# wemos_gpio_7x.net
KiCad netlist of a schematic drawn in EAGLE
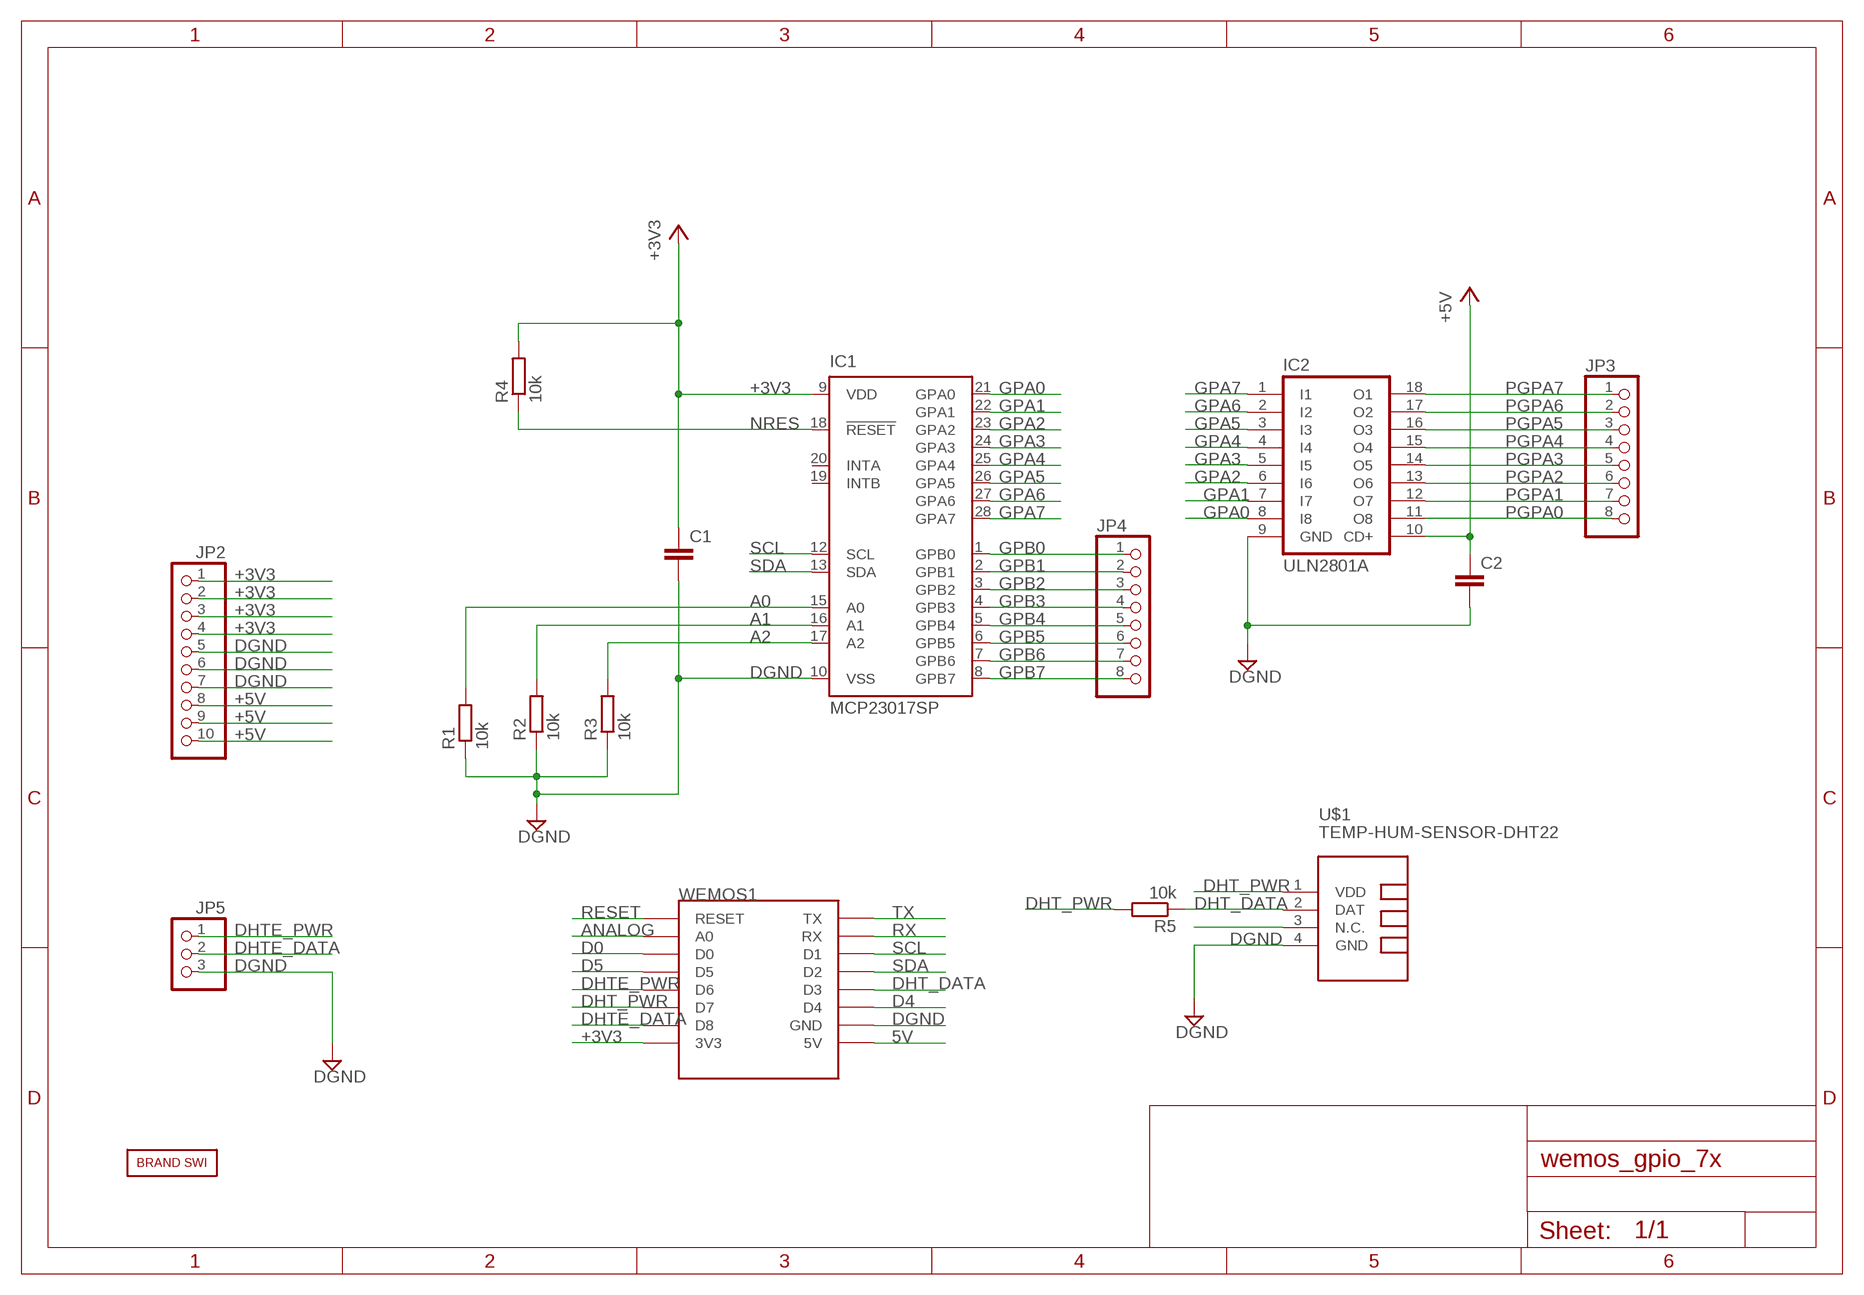
[diagram p0: schematic, sheet 1]

(export (version "E")
  (design (tool "Eeschema 10.0.6"))
  (components
    (comp (ref "C1")
      (value "C-EUC1210")
      (footprint "eagle-import:C1210")
      (libsource (lib "eagle-import") (part "C-EUC1210"))
    )
    (comp (ref "C2")
      (value "C-EUC1210")
      (footprint "eagle-import:C1210")
      (libsource (lib "eagle-import") (part "C-EUC1210"))
    )
    (comp (ref "IC1")
      (value "MCP23017SP")
      (footprint "eagle-import:DIL28-3")
      (fields (field (name "MF") "MICROCHIP") (field (name "MPN") "MCP23017-E/SP"))
      (libsource (lib "eagle-import") (part "MCP23017SP"))
    )
    (comp (ref "IC2")
      (value "ULN2801A")
      (footprint "eagle-import:DIL18")
      (libsource (lib "eagle-import") (part "ULN2801A"))
    )
    (comp (ref "JP2")
      (value "PINHD-1X10")
      (footprint "eagle-import:1X10")
      (libsource (lib "eagle-import") (part "PINHD-1X10"))
    )
    (comp (ref "JP3")
      (value "PINHD-1X8")
      (footprint "eagle-import:1X08")
      (libsource (lib "eagle-import") (part "PINHD-1X8"))
    )
    (comp (ref "JP4")
      (value "PINHD-1X8")
      (footprint "eagle-import:1X08")
      (libsource (lib "eagle-import") (part "PINHD-1X8"))
    )
    (comp (ref "JP5")
      (value "PINHD-1X3")
      (footprint "eagle-import:1X03")
      (libsource (lib "eagle-import") (part "PINHD-1X3"))
    )
    (comp (ref "R1")
      (value "10k")
      (footprint "eagle-import:M1206")
      (libsource (lib "eagle-import") (part "R-EU_M1206"))
    )
    (comp (ref "R2")
      (value "10k")
      (footprint "eagle-import:M1206")
      (libsource (lib "eagle-import") (part "R-EU_M1206"))
    )
    (comp (ref "R3")
      (value "10k")
      (footprint "eagle-import:M1206")
      (libsource (lib "eagle-import") (part "R-EU_M1206"))
    )
    (comp (ref "R4")
      (value "10k")
      (footprint "eagle-import:M1206")
      (libsource (lib "eagle-import") (part "R-EU_M1206"))
    )
    (comp (ref "R5")
      (value "10k")
      (footprint "eagle-import:M1206")
      (libsource (lib "eagle-import") (part "R-EU_M1206"))
    )
    (comp (ref "U$1")
      (value "TEMP-HUM-SENSOR-DHT22")
      (footprint "eagle-import:TEMP-HUM-SENSOR-DHT22")
      (libsource (lib "eagle-import") (part "TEMP-HUM-SENSOR-DHT22"))
    )
    (comp (ref "U$2")
      (value "BRAND_SWI5X7")
      (footprint "eagle-import:BRAND_SWI_5X7")
      (libsource (lib "eagle-import") (part "BRAND_SWI5X7"))
    )
    (comp (ref "WEMOS1")
      (value "WEMOS-D1-MINI")
      (footprint "eagle-import:WEMOS-D1-MINI")
      (libsource (lib "eagle-import") (part "WEMOS-D1-MINI"))
    )
  )
  (nets
    (net (code "1") (name "+3V3") (class "Default")
      (node (ref "C1") (pin "1") (pinfunction "1_1") (pintype "passive"))
      (node (ref "IC1") (pin "9") (pinfunction "VDD_9") (pintype "power_in"))
      (node (ref "JP2") (pin "1") (pinfunction "1_1") (pintype "passive"))
      (node (ref "JP2") (pin "2") (pinfunction "2_2") (pintype "passive"))
      (node (ref "JP2") (pin "3") (pinfunction "3_3") (pintype "passive"))
      (node (ref "JP2") (pin "4") (pinfunction "4_4") (pintype "passive"))
      (node (ref "R4") (pin "2") (pinfunction "2_2") (pintype "passive"))
      (node (ref "WEMOS1") (pin "3V3") (pinfunction "3V3_3V3") (pintype "bidirectional"))
    )
    (net (code "2") (name "+5V") (class "Default")
      (node (ref "C2") (pin "1") (pinfunction "1_1") (pintype "passive"))
      (node (ref "IC2") (pin "10") (pinfunction "CD+_10") (pintype "passive"))
      (node (ref "JP2") (pin "10") (pinfunction "10_10") (pintype "passive"))
      (node (ref "JP2") (pin "8") (pinfunction "8_8") (pintype "passive"))
      (node (ref "JP2") (pin "9") (pinfunction "9_9") (pintype "passive"))
    )
    (net (code "3") (name "/5V") (class "Default")
      (node (ref "WEMOS1") (pin "5V") (pinfunction "5V_5V") (pintype "bidirectional"))
    )
    (net (code "4") (name "/A0") (class "Default")
      (node (ref "IC1") (pin "15") (pinfunction "A0_15") (pintype "input"))
      (node (ref "R1") (pin "2") (pinfunction "2_2") (pintype "passive"))
    )
    (net (code "5") (name "/A1") (class "Default")
      (node (ref "IC1") (pin "16") (pinfunction "A1_16") (pintype "input"))
      (node (ref "R2") (pin "2") (pinfunction "2_2") (pintype "passive"))
    )
    (net (code "6") (name "/A2") (class "Default")
      (node (ref "IC1") (pin "17") (pinfunction "A2_17") (pintype "input"))
      (node (ref "R3") (pin "2") (pinfunction "2_2") (pintype "passive"))
    )
    (net (code "7") (name "/ANALOG") (class "Default")
      (node (ref "WEMOS1") (pin "A0") (pinfunction "A0_A0") (pintype "bidirectional"))
    )
    (net (code "8") (name "/D0") (class "Default")
      (node (ref "WEMOS1") (pin "D0") (pinfunction "D0_D0") (pintype "bidirectional"))
    )
    (net (code "9") (name "/D4") (class "Default")
      (node (ref "WEMOS1") (pin "D4") (pinfunction "D4_D4") (pintype "bidirectional"))
    )
    (net (code "10") (name "/D5") (class "Default")
      (node (ref "WEMOS1") (pin "D5") (pinfunction "D5_D5") (pintype "bidirectional"))
    )
    (net (code "11") (name "/DHTE_DATA") (class "Default")
      (node (ref "JP5") (pin "2") (pinfunction "2_2") (pintype "passive"))
      (node (ref "WEMOS1") (pin "D8") (pinfunction "D8_D8") (pintype "bidirectional"))
    )
    (net (code "12") (name "/DHTE_PWR") (class "Default")
      (node (ref "JP5") (pin "1") (pinfunction "1_1") (pintype "passive"))
      (node (ref "WEMOS1") (pin "D6") (pinfunction "D6_D6") (pintype "bidirectional"))
    )
    (net (code "13") (name "/DHT_DATA") (class "Default")
      (node (ref "R5") (pin "1") (pinfunction "1_1") (pintype "passive"))
      (node (ref "U$1") (pin "2") (pinfunction "DAT_2") (pintype "bidirectional"))
      (node (ref "WEMOS1") (pin "D3") (pinfunction "D3_D3") (pintype "bidirectional"))
    )
    (net (code "14") (name "/DHT_PWR") (class "Default")
      (node (ref "R5") (pin "2") (pinfunction "2_2") (pintype "passive"))
      (node (ref "U$1") (pin "1") (pinfunction "VDD_1") (pintype "power_in"))
      (node (ref "WEMOS1") (pin "D7") (pinfunction "D7_D7") (pintype "bidirectional"))
    )
    (net (code "15") (name "/GPA0") (class "Default")
      (node (ref "IC1") (pin "21") (pinfunction "GPA0_21") (pintype "bidirectional"))
      (node (ref "IC2") (pin "8") (pinfunction "I8_8") (pintype "input"))
    )
    (net (code "16") (name "/GPA1") (class "Default")
      (node (ref "IC1") (pin "22") (pinfunction "GPA1_22") (pintype "bidirectional"))
      (node (ref "IC2") (pin "7") (pinfunction "I7_7") (pintype "input"))
    )
    (net (code "17") (name "/GPA2") (class "Default")
      (node (ref "IC1") (pin "23") (pinfunction "GPA2_23") (pintype "bidirectional"))
      (node (ref "IC2") (pin "6") (pinfunction "I6_6") (pintype "input"))
    )
    (net (code "18") (name "/GPA3") (class "Default")
      (node (ref "IC1") (pin "24") (pinfunction "GPA3_24") (pintype "bidirectional"))
      (node (ref "IC2") (pin "5") (pinfunction "I5_5") (pintype "input"))
    )
    (net (code "19") (name "/GPA4") (class "Default")
      (node (ref "IC1") (pin "25") (pinfunction "GPA4_25") (pintype "bidirectional"))
      (node (ref "IC2") (pin "4") (pinfunction "I4_4") (pintype "input"))
    )
    (net (code "20") (name "/GPA5") (class "Default")
      (node (ref "IC1") (pin "26") (pinfunction "GPA5_26") (pintype "bidirectional"))
      (node (ref "IC2") (pin "3") (pinfunction "I3_3") (pintype "input"))
    )
    (net (code "21") (name "/GPA6") (class "Default")
      (node (ref "IC1") (pin "27") (pinfunction "GPA6_27") (pintype "bidirectional"))
      (node (ref "IC2") (pin "2") (pinfunction "I2_2") (pintype "input"))
    )
    (net (code "22") (name "/GPA7") (class "Default")
      (node (ref "IC1") (pin "28") (pinfunction "GPA7_28") (pintype "bidirectional"))
      (node (ref "IC2") (pin "1") (pinfunction "I1_1") (pintype "input"))
    )
    (net (code "23") (name "/GPB0") (class "Default")
      (node (ref "IC1") (pin "1") (pinfunction "GPB0_1") (pintype "bidirectional"))
      (node (ref "JP4") (pin "1") (pinfunction "1_1") (pintype "passive"))
    )
    (net (code "24") (name "/GPB1") (class "Default")
      (node (ref "IC1") (pin "2") (pinfunction "GPB1_2") (pintype "bidirectional"))
      (node (ref "JP4") (pin "2") (pinfunction "2_2") (pintype "passive"))
    )
    (net (code "25") (name "/GPB2") (class "Default")
      (node (ref "IC1") (pin "3") (pinfunction "GPB2_3") (pintype "bidirectional"))
      (node (ref "JP4") (pin "3") (pinfunction "3_3") (pintype "passive"))
    )
    (net (code "26") (name "/GPB3") (class "Default")
      (node (ref "IC1") (pin "4") (pinfunction "GPB3_4") (pintype "bidirectional"))
      (node (ref "JP4") (pin "4") (pinfunction "4_4") (pintype "passive"))
    )
    (net (code "27") (name "/GPB4") (class "Default")
      (node (ref "IC1") (pin "5") (pinfunction "GPB4_5") (pintype "bidirectional"))
      (node (ref "JP4") (pin "5") (pinfunction "5_5") (pintype "passive"))
    )
    (net (code "28") (name "/GPB5") (class "Default")
      (node (ref "IC1") (pin "6") (pinfunction "GPB5_6") (pintype "bidirectional"))
      (node (ref "JP4") (pin "6") (pinfunction "6_6") (pintype "passive"))
    )
    (net (code "29") (name "/GPB6") (class "Default")
      (node (ref "IC1") (pin "7") (pinfunction "GPB6_7") (pintype "bidirectional"))
      (node (ref "JP4") (pin "7") (pinfunction "7_7") (pintype "passive"))
    )
    (net (code "30") (name "/GPB7") (class "Default")
      (node (ref "IC1") (pin "8") (pinfunction "GPB7_8") (pintype "bidirectional"))
      (node (ref "JP4") (pin "8") (pinfunction "8_8") (pintype "passive"))
    )
    (net (code "31") (name "/NRES") (class "Default")
      (node (ref "IC1") (pin "18") (pinfunction "~{RESET}_18") (pintype "input"))
      (node (ref "R4") (pin "1") (pinfunction "1_1") (pintype "passive"))
    )
    (net (code "32") (name "/PGPA0") (class "Default")
      (node (ref "IC2") (pin "11") (pinfunction "O8_11") (pintype "open_collector"))
      (node (ref "JP3") (pin "8") (pinfunction "8_8") (pintype "passive"))
    )
    (net (code "33") (name "/PGPA1") (class "Default")
      (node (ref "IC2") (pin "12") (pinfunction "O7_12") (pintype "open_collector"))
      (node (ref "JP3") (pin "7") (pinfunction "7_7") (pintype "passive"))
    )
    (net (code "34") (name "/PGPA2") (class "Default")
      (node (ref "IC2") (pin "13") (pinfunction "O6_13") (pintype "open_collector"))
      (node (ref "JP3") (pin "6") (pinfunction "6_6") (pintype "passive"))
    )
    (net (code "35") (name "/PGPA3") (class "Default")
      (node (ref "IC2") (pin "14") (pinfunction "O5_14") (pintype "open_collector"))
      (node (ref "JP3") (pin "5") (pinfunction "5_5") (pintype "passive"))
    )
    (net (code "36") (name "/PGPA4") (class "Default")
      (node (ref "IC2") (pin "15") (pinfunction "O4_15") (pintype "open_collector"))
      (node (ref "JP3") (pin "4") (pinfunction "4_4") (pintype "passive"))
    )
    (net (code "37") (name "/PGPA5") (class "Default")
      (node (ref "IC2") (pin "16") (pinfunction "O3_16") (pintype "open_collector"))
      (node (ref "JP3") (pin "3") (pinfunction "3_3") (pintype "passive"))
    )
    (net (code "38") (name "/PGPA6") (class "Default")
      (node (ref "IC2") (pin "17") (pinfunction "O2_17") (pintype "open_collector"))
      (node (ref "JP3") (pin "2") (pinfunction "2_2") (pintype "passive"))
    )
    (net (code "39") (name "/PGPA7") (class "Default")
      (node (ref "IC2") (pin "18") (pinfunction "O1_18") (pintype "open_collector"))
      (node (ref "JP3") (pin "1") (pinfunction "1_1") (pintype "passive"))
    )
    (net (code "40") (name "/RESET") (class "Default")
      (node (ref "WEMOS1") (pin "RESET") (pinfunction "RESET_RESET") (pintype "bidirectional"))
    )
    (net (code "41") (name "/RX") (class "Default")
      (node (ref "WEMOS1") (pin "RX") (pinfunction "RX_RX") (pintype "bidirectional"))
    )
    (net (code "42") (name "/SCL") (class "Default")
      (node (ref "IC1") (pin "12") (pinfunction "SCL_12") (pintype "input"))
      (node (ref "WEMOS1") (pin "D1") (pinfunction "D1_D1") (pintype "bidirectional"))
    )
    (net (code "43") (name "/SDA") (class "Default")
      (node (ref "IC1") (pin "13") (pinfunction "SDA_13") (pintype "bidirectional"))
      (node (ref "WEMOS1") (pin "D2") (pinfunction "D2_D2") (pintype "bidirectional"))
    )
    (net (code "44") (name "/TX") (class "Default")
      (node (ref "WEMOS1") (pin "TX") (pinfunction "TX_TX") (pintype "bidirectional"))
    )
    (net (code "45") (name "DGND") (class "Default")
      (node (ref "C1") (pin "2") (pinfunction "2_2") (pintype "passive"))
      (node (ref "C2") (pin "2") (pinfunction "2_2") (pintype "passive"))
      (node (ref "IC1") (pin "10") (pinfunction "VSS_10") (pintype "power_in"))
      (node (ref "IC2") (pin "9") (pinfunction "GND_9") (pintype "power_in"))
      (node (ref "JP2") (pin "5") (pinfunction "5_5") (pintype "passive"))
      (node (ref "JP2") (pin "6") (pinfunction "6_6") (pintype "passive"))
      (node (ref "JP2") (pin "7") (pinfunction "7_7") (pintype "passive"))
      (node (ref "JP5") (pin "3") (pinfunction "3_3") (pintype "passive"))
      (node (ref "R1") (pin "1") (pinfunction "1_1") (pintype "passive"))
      (node (ref "R2") (pin "1") (pinfunction "1_1") (pintype "passive"))
      (node (ref "R3") (pin "1") (pinfunction "1_1") (pintype "passive"))
      (node (ref "U$1") (pin "4") (pinfunction "GND_4") (pintype "power_in"))
      (node (ref "WEMOS1") (pin "GND") (pinfunction "GND_GND") (pintype "bidirectional"))
    )
    (net (code "46") (name "unconnected-(IC1-INTA-Pad20)") (class "Default")
      (node (ref "IC1") (pin "20") (pinfunction "INTA_20") (pintype "output"))
    )
    (net (code "47") (name "unconnected-(IC1-INTB-Pad19)") (class "Default")
      (node (ref "IC1") (pin "19") (pinfunction "INTB_19") (pintype "output"))
    )
    (net (code "48") (name "unconnected-(U$1-N.C.-Pad3)") (class "Default")
      (node (ref "U$1") (pin "3") (pinfunction "N.C._3") (pintype "passive"))
    )
  )
)
